# LV_solo_mission_schematic.net
KiCad netlist of a schematic drawn in Altium Designer
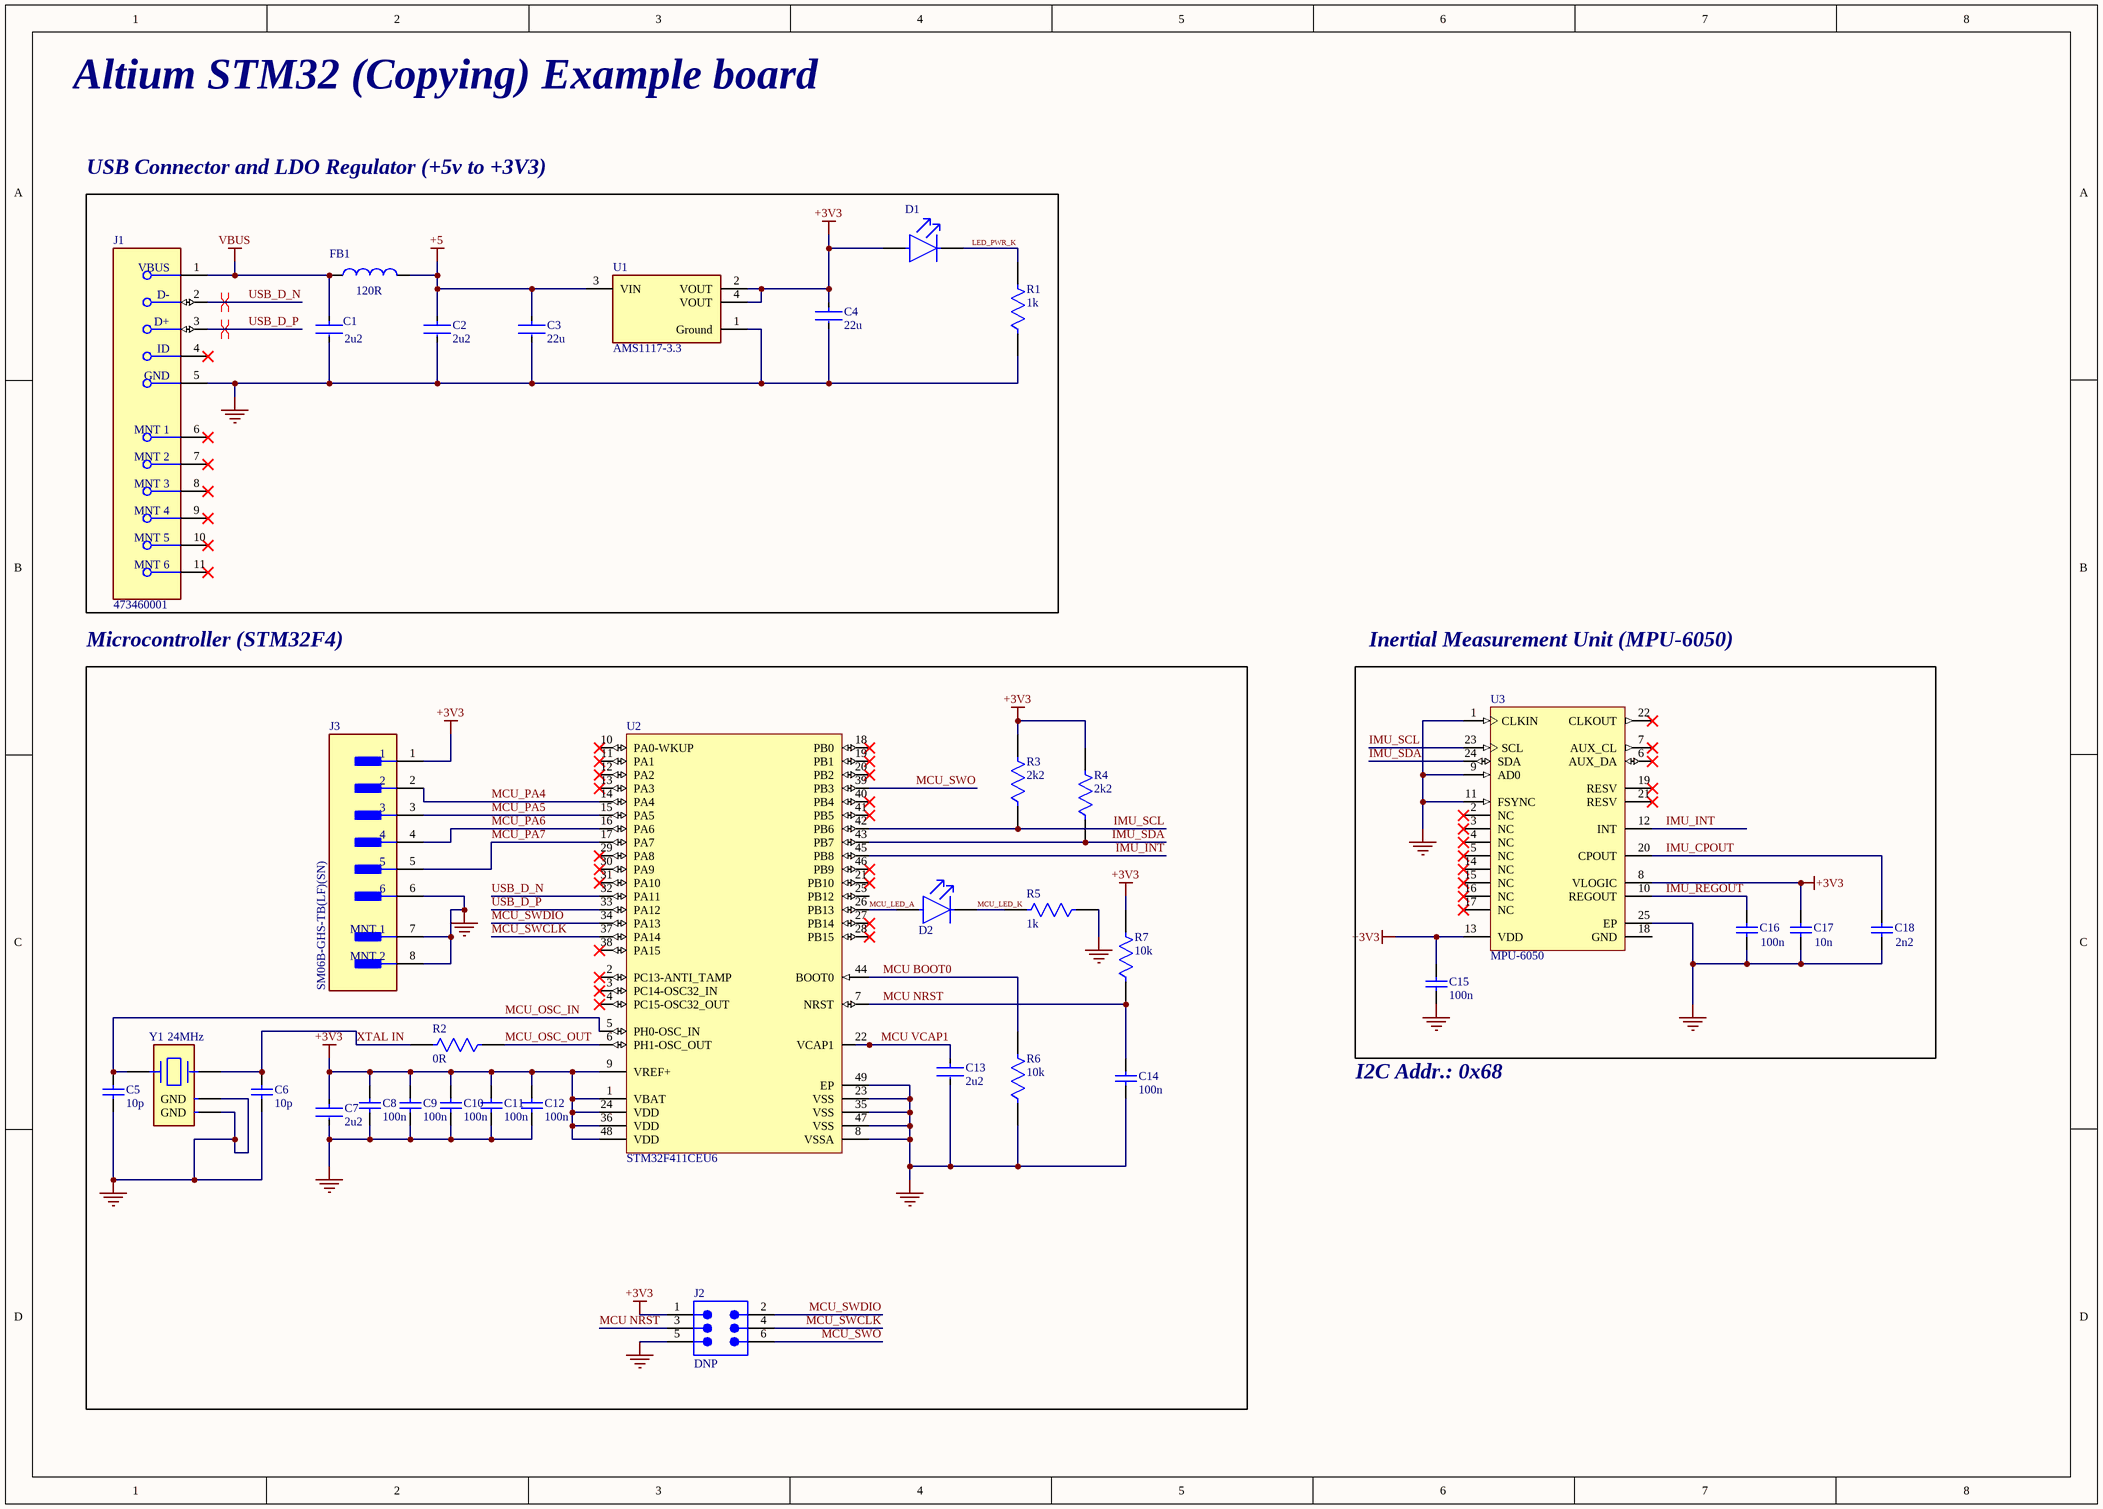
[diagram p0: LV solo mission schematic.SchDoc]

(export (version "E")
  (design (tool "Eeschema 10.0.6"))
  (components
    (comp (ref "C1")
      (value "2u2")
      (footprint "FP-GRM188-0_2-IPC_B")
      (description "CAP CER 2.2UF 16V X7S 0603")
      (fields (field (name "TOLERANCE") "10%"))
      (libsource (lib "Altium Content Vault") (part "b4654b650e69147ec39a6b967a45e02"))
    )
    (comp (ref "C2")
      (value "2u2")
      (footprint "FP-GRM188-0_2-IPC_B")
      (description "CAP CER 2.2UF 16V X7S 0603")
      (fields (field (name "TOLERANCE") "10%"))
      (libsource (lib "Altium Content Vault") (part "b4654b650e69147ec39a6b967a45e02"))
    )
    (comp (ref "C3")
      (value "22u")
      (footprint "FP-GRM21B-0_2-e0_2_0_7-MFG")
      (description "Chip Multilayer Ceramic Capacitors for General Purpose, 0805, 22uF, X6S, 22%, 20%, 16V")
      (fields (field (name "TOLERANCE") "20%"))
      (libsource (lib "Altium Content Vault") (part "b4654b650e69147ec39a6b967a45e02"))
    )
    (comp (ref "C4")
      (value "22u")
      (footprint "FP-GRM21B-0_2-e0_2_0_7-MFG")
      (description "Chip Multilayer Ceramic Capacitors for General Purpose, 0805, 22uF, X6S, 22%, 20%, 16V")
      (fields (field (name "TOLERANCE") "20%"))
      (libsource (lib "Altium Content Vault") (part "b4654b650e69147ec39a6b967a45e02"))
    )
    (comp (ref "C5")
      (value "10p")
      (footprint "CAPC1005X55X25LL05T05")
      (fields (field (name "PART NUMBER") "VJ0402A100KXJCW1BC") (field (name "MANUFACTURER") "Vitramon"))
      (libsource (lib "Altium Content Vault") (part "CAP"))
    )
    (comp (ref "C6")
      (value "10p")
      (footprint "CAPC1005X55X25LL05T05")
      (fields (field (name "PART NUMBER") "VJ0402A100KXJCW1BC") (field (name "MANUFACTURER") "Vitramon"))
      (libsource (lib "Altium Content Vault") (part "CAP"))
    )
    (comp (ref "C7")
      (value "2u2")
      (footprint "FP-GRM188-0_2-IPC_B")
      (description "CAP CER 2.2UF 16V X7S 0603")
      (fields (field (name "TOLERANCE") "10%"))
      (libsource (lib "Altium Content Vault") (part "b4654b650e69147ec39a6b967a45e02"))
    )
    (comp (ref "C8")
      (value "100n")
      (footprint "CAPC1005X55X30NL05T10")
      (fields (field (name "PART NUMBER") "C0402C104K4RALTU") (field (name "MANUFACTURER") "Kemet"))
      (libsource (lib "Altium Content Vault") (part "CAP"))
    )
    (comp (ref "C9")
      (value "100n")
      (footprint "CAPC1005X55X30NL05T10")
      (fields (field (name "PART NUMBER") "C0402C104K4RALTU") (field (name "MANUFACTURER") "Kemet"))
      (libsource (lib "Altium Content Vault") (part "CAP"))
    )
    (comp (ref "C10")
      (value "100n")
      (footprint "CAPC1005X55X30NL05T10")
      (fields (field (name "PART NUMBER") "C0402C104K4RALTU") (field (name "MANUFACTURER") "Kemet"))
      (libsource (lib "Altium Content Vault") (part "CAP"))
    )
    (comp (ref "C11")
      (value "100n")
      (footprint "CAPC1005X55X30NL05T10")
      (fields (field (name "PART NUMBER") "C0402C104K4RALTU") (field (name "MANUFACTURER") "Kemet"))
      (libsource (lib "Altium Content Vault") (part "CAP"))
    )
    (comp (ref "C12")
      (value "100n")
      (footprint "CAPC1005X55X30NL05T10")
      (fields (field (name "PART NUMBER") "C0402C104K4RALTU") (field (name "MANUFACTURER") "Kemet"))
      (libsource (lib "Altium Content Vault") (part "CAP"))
    )
    (comp (ref "C13")
      (value "2u2")
      (footprint "FP-GRM188-0_2-IPC_B")
      (description "CAP CER 2.2UF 16V X7S 0603")
      (fields (field (name "TOLERANCE") "10%"))
      (libsource (lib "Altium Content Vault") (part "b4654b650e69147ec39a6b967a45e02"))
    )
    (comp (ref "C14")
      (value "100n")
      (footprint "CAPC1005X55X30NL05T10")
      (fields (field (name "PART NUMBER") "C0402C104K4RALTU") (field (name "MANUFACTURER") "Kemet"))
      (libsource (lib "Altium Content Vault") (part "CAP"))
    )
    (comp (ref "C15")
      (value "100n")
      (footprint "CAPC1005X55X30NL05T10")
      (fields (field (name "PART NUMBER") "C0402C104K4RALTU") (field (name "MANUFACTURER") "Kemet"))
      (libsource (lib "Altium Content Vault") (part "CAP"))
    )
    (comp (ref "C16")
      (value "100n")
      (footprint "CAPC1005X55X30NL05T10")
      (fields (field (name "PART NUMBER") "C0402C104K4RALTU") (field (name "MANUFACTURER") "Kemet"))
      (libsource (lib "Altium Content Vault") (part "CAP"))
    )
    (comp (ref "C17")
      (value "10n")
      (footprint "CAPC1005X55X30NL05T10")
      (fields (field (name "PART NUMBER") "C0402C104K4RALTU") (field (name "MANUFACTURER") "Kemet"))
      (libsource (lib "Altium Content Vault") (part "CAP"))
    )
    (comp (ref "C18")
      (value "2n2")
      (footprint "CAPC1005X55X30NL05T10")
      (fields (field (name "PART NUMBER") "C0402C104K4RALTU") (field (name "MANUFACTURER") "Kemet"))
      (libsource (lib "Altium Content Vault") (part "CAP"))
    )
    (comp (ref "D1")
      (value "~")
      (footprint "FP-APG1005CGC-T-MFG")
      (description "LED GREEN CLEAR CHIP SMD")
      (libsource (lib "Altium Content Vault") (part "8706943c75ba83719d021d2fdc84c58"))
    )
    (comp (ref "D2")
      (value "APHHS1005SURCK")
      (footprint "FP-APHHS1005SURCK-MFG")
      (description "LED RED CLEAR CHIP SMD")
      (libsource (lib "Altium Content Vault") (part "8706943c75ba83719d021d2fdc84c58"))
    )
    (comp (ref "FB1")
      (value "120R")
      (footprint "WE-CBF HF_0603_HC")
      (description "Ferrite Bead (emi Suppression), 1.6X0.8X0.8MM (0603), 600O Impedance At 100 Mhz")
      (fields (field (name "TOLERANCE") "25%"))
      (libsource (lib "Altium Content Vault") (part "Ferrite"))
    )
    (comp (ref "J1")
      (value "473460001")
      (footprint "FP-473460001-MFG")
      (description "CONN RCPT USB2.0 MICRO B SMD R/A")
      (fields
        (field (name "OCTOPART") "https://octopart.com/47346-0001-molex-7164928")
        (field (name "MANUFACTURER") "Molex")
      )
      (libsource (lib "Altium Content Vault") (part "53ae1f1d9b557310b43ca686e5bb76a"))
    )
    (comp (ref "J2")
      (value "DNP")
      (footprint "61300621121")
      (description "THT Vertical Pin Header WR-PHD, Pitch 2.54 mm, Dual Row, 6 pins")
      (libsource (lib "Altium Content Vault") (part "Header_Male_2R_06P"))
    )
    (comp (ref "J3")
      (value "SM06B-GHS-TB(LF)(SN)")
      (footprint "FP-SM06B-GHS-TB_LF_SN-MFG")
      (description "CONN HEADER SMD R/A 6POS 1.25MM")
      (libsource (lib "Altium Content Vault") (part "ed24c53d9ba001d1a2a686240a95171"))
    )
    (comp (ref "R1")
      (value "1k")
      (footprint "FP-CR0402-MFG")
      (description "Sulfur-Resistant, AEC-Q200 Compliant Chip Resistors 0402 10kΩ 0.063W 1% 100ppm/°C")
      (libsource (lib "Altium Content Vault") (part "1029c3af85768c4190bb7ad29bc67b5"))
    )
    (comp (ref "R2")
      (value "0R")
      (footprint "FP-CR0402-MFG")
      (description "Sulfur-Resistant, AEC-Q200 Compliant Chip Resistors 0402 10kΩ 0.063W 1% 100ppm/°C")
      (libsource (lib "Altium Content Vault") (part "1029c3af85768c4190bb7ad29bc67b5"))
    )
    (comp (ref "R3")
      (value "2k2")
      (footprint "FP-CR0402-MFG")
      (description "Sulfur-Resistant, AEC-Q200 Compliant Chip Resistors 0402 10kΩ 0.063W 1% 100ppm/°C")
      (libsource (lib "Altium Content Vault") (part "1029c3af85768c4190bb7ad29bc67b5"))
    )
    (comp (ref "R4")
      (value "2k2")
      (footprint "FP-CR0402-MFG")
      (description "Sulfur-Resistant, AEC-Q200 Compliant Chip Resistors 0402 10kΩ 0.063W 1% 100ppm/°C")
      (libsource (lib "Altium Content Vault") (part "1029c3af85768c4190bb7ad29bc67b5"))
    )
    (comp (ref "R5")
      (value "1k")
      (footprint "FP-CR0402-MFG")
      (description "Sulfur-Resistant, AEC-Q200 Compliant Chip Resistors 0402 10kΩ 0.063W 1% 100ppm/°C")
      (libsource (lib "Altium Content Vault") (part "1029c3af85768c4190bb7ad29bc67b5"))
    )
    (comp (ref "R6")
      (value "10k")
      (footprint "FP-CR0402-MFG")
      (description "Sulfur-Resistant, AEC-Q200 Compliant Chip Resistors 0402 10kΩ 0.063W 1% 100ppm/°C")
      (libsource (lib "Altium Content Vault") (part "1029c3af85768c4190bb7ad29bc67b5"))
    )
    (comp (ref "R7")
      (value "10k")
      (footprint "FP-CR0402-MFG")
      (description "Sulfur-Resistant, AEC-Q200 Compliant Chip Resistors 0402 10kΩ 0.063W 1% 100ppm/°C")
      (libsource (lib "Altium Content Vault") (part "1029c3af85768c4190bb7ad29bc67b5"))
    )
    (comp (ref "U1")
      (value "AMS1117-3.3")
      (footprint "FP-AMS1117-IPC_C")
      (description "LDO Voltage Regulators 1A, 3.3V")
      (fields
        (field (name "OCTOPART") "https://octopart.com/ams1117-3.3-advanced+monolithic+systems-25899300")
        (field (name "MANUFACTURER") "Advanced Monolithic Systems")
      )
      (libsource (lib "Altium Content Vault") (part "8bdbb5f8e77002000e30dd2845d0354"))
    )
    (comp (ref "U2")
      (value "STM32F411CEU6")
      (footprint "STM-UFQFPN48_L")
      (libsource (lib "Altium Content Vault") (part "MC-ARM-STM32F411-UFQFPN48"))
    )
    (comp (ref "U3")
      (value "MPU-6050")
      (footprint "IS-QFN-24_V")
      (fields (field (name "MANUFACTURER") "InvenSense"))
      (libsource (lib "Altium Content Vault") (part "IS-MPU-6050-QFN-24"))
    )
    (comp (ref "Y1")
      (value "24MHz")
      (footprint "FP-ABM8W-MFG")
      (description "Crystal 24MHz ±10ppm (Tol) ±10ppm (Stability) 7pF FUND 50Ω 4-Pin SMD T/R")
      (libsource (lib "Altium Content Vault") (part "41079aabb0e87794b56622915be14ed"))
    )
  )
  (nets
    (net (code "1") (name "+3V3") (class "Default")
      (node (ref "C10") (pin "1") (pinfunction "1_1") (pintype "passive"))
      (node (ref "C11") (pin "1") (pinfunction "1_1") (pintype "passive"))
      (node (ref "C12") (pin "1") (pinfunction "1_1") (pintype "passive"))
      (node (ref "C15") (pin "1") (pinfunction "1_1") (pintype "passive"))
      (node (ref "C17") (pin "1") (pinfunction "1_1") (pintype "passive"))
      (node (ref "C4") (pin "1") (pinfunction "1_1") (pintype "passive"))
      (node (ref "C7") (pin "1") (pinfunction "1_1") (pintype "passive"))
      (node (ref "C8") (pin "1") (pinfunction "1_1") (pintype "passive"))
      (node (ref "C9") (pin "1") (pinfunction "1_1") (pintype "passive"))
      (node (ref "D1") (pin "2") (pinfunction "A_2") (pintype "passive"))
      (node (ref "J2") (pin "1") (pinfunction "1_1") (pintype "passive"))
      (node (ref "J3") (pin "1") (pinfunction "1_1") (pintype "passive"))
      (node (ref "R3") (pin "2") (pinfunction "2_2") (pintype "passive"))
      (node (ref "R4") (pin "2") (pinfunction "2_2") (pintype "passive"))
      (node (ref "R7") (pin "2") (pinfunction "2_2") (pintype "passive"))
      (node (ref "U1") (pin "2") (pinfunction "VOUT_2") (pintype "passive"))
      (node (ref "U1") (pin "4") (pinfunction "VOUT_4") (pintype "passive"))
      (node (ref "U2") (pin "1") (pinfunction "VBAT_1") (pintype "power_in"))
      (node (ref "U2") (pin "24") (pinfunction "VDD_24") (pintype "power_in"))
      (node (ref "U2") (pin "36") (pinfunction "VDD_36") (pintype "power_in"))
      (node (ref "U2") (pin "48") (pinfunction "VDD_48") (pintype "power_in"))
      (node (ref "U2") (pin "9") (pinfunction "VREF+_9") (pintype "power_in"))
      (node (ref "U3") (pin "13") (pinfunction "VDD_13") (pintype "power_in"))
      (node (ref "U3") (pin "8") (pinfunction "VLOGIC_8") (pintype "power_in"))
    )
    (net (code "2") (name "+5") (class "Default")
      (node (ref "C2") (pin "1") (pinfunction "1_1") (pintype "passive"))
      (node (ref "C3") (pin "1") (pinfunction "1_1") (pintype "passive"))
      (node (ref "FB1") (pin "2") (pinfunction "2_2") (pintype "passive"))
      (node (ref "U1") (pin "3") (pinfunction "VIN_3") (pintype "power_in"))
    )
    (net (code "3") (name "/IMU_CPOUT") (class "Default")
      (node (ref "C18") (pin "1") (pinfunction "1_1") (pintype "passive"))
      (node (ref "U3") (pin "20") (pinfunction "CPOUT_20") (pintype "passive"))
    )
    (net (code "4") (name "/IMU_INT") (class "Default")
      (node (ref "U2") (pin "45") (pinfunction "PB8_45") (pintype "bidirectional"))
      (node (ref "U3") (pin "12") (pinfunction "INT_12") (pintype "open_collector"))
    )
    (net (code "5") (name "/IMU_REGOUT") (class "Default")
      (node (ref "C16") (pin "1") (pinfunction "1_1") (pintype "passive"))
      (node (ref "U3") (pin "10") (pinfunction "REGOUT_10") (pintype "passive"))
    )
    (net (code "6") (name "/IMU_SCL") (class "Default")
      (node (ref "R3") (pin "1") (pinfunction "1_1") (pintype "passive"))
      (node (ref "U2") (pin "42") (pinfunction "PB6_42") (pintype "bidirectional"))
      (node (ref "U3") (pin "23") (pinfunction "SCL_23") (pintype "input"))
    )
    (net (code "7") (name "/IMU_SDA") (class "Default")
      (node (ref "R4") (pin "1") (pinfunction "1_1") (pintype "passive"))
      (node (ref "U2") (pin "43") (pinfunction "PB7_43") (pintype "bidirectional"))
      (node (ref "U3") (pin "24") (pinfunction "SDA_24") (pintype "bidirectional"))
    )
    (net (code "8") (name "/LED_PWR_K") (class "Default")
      (node (ref "D1") (pin "1") (pinfunction "C_1") (pintype "passive"))
      (node (ref "R1") (pin "2") (pinfunction "2_2") (pintype "passive"))
    )
    (net (code "9") (name "/MCU BOOT0") (class "Default")
      (node (ref "R6") (pin "2") (pinfunction "2_2") (pintype "passive"))
      (node (ref "U2") (pin "44") (pinfunction "BOOT0_44") (pintype "input"))
    )
    (net (code "10") (name "/MCU NRST") (class "Default")
      (node (ref "C14") (pin "1") (pinfunction "1_1") (pintype "passive"))
      (node (ref "J2") (pin "3") (pinfunction "3_3") (pintype "passive"))
      (node (ref "R7") (pin "1") (pinfunction "1_1") (pintype "passive"))
      (node (ref "U2") (pin "7") (pinfunction "NRST_7") (pintype "bidirectional"))
    )
    (net (code "11") (name "/MCU VCAP1") (class "Default")
      (node (ref "C13") (pin "1") (pinfunction "1_1") (pintype "passive"))
      (node (ref "U2") (pin "22") (pinfunction "VCAP1_22") (pintype "passive"))
    )
    (net (code "12") (name "/MCU_LED_A") (class "Default")
      (node (ref "D2") (pin "2") (pinfunction "A_2") (pintype "passive"))
      (node (ref "U2") (pin "26") (pinfunction "PB13_26") (pintype "bidirectional"))
    )
    (net (code "13") (name "/MCU_LED_K") (class "Default")
      (node (ref "D2") (pin "1") (pinfunction "C_1") (pintype "passive"))
      (node (ref "R5") (pin "2") (pinfunction "2_2") (pintype "passive"))
    )
    (net (code "14") (name "/MCU_OSC_IN") (class "Default")
      (node (ref "C5") (pin "2") (pinfunction "2_2") (pintype "passive"))
      (node (ref "U2") (pin "5") (pinfunction "PH0-OSC_IN_5") (pintype "bidirectional"))
      (node (ref "Y1") (pin "1") (pinfunction "1_1") (pintype "passive"))
    )
    (net (code "15") (name "/MCU_OSC_OUT") (class "Default")
      (node (ref "R2") (pin "1") (pinfunction "1_1") (pintype "passive"))
      (node (ref "U2") (pin "6") (pinfunction "PH1-OSC_OUT_6") (pintype "bidirectional"))
    )
    (net (code "16") (name "/MCU_PA4") (class "Default")
      (node (ref "J3") (pin "2") (pinfunction "2_2") (pintype "passive"))
      (node (ref "U2") (pin "14") (pinfunction "PA4_14") (pintype "bidirectional"))
    )
    (net (code "17") (name "/MCU_PA5") (class "Default")
      (node (ref "J3") (pin "3") (pinfunction "3_3") (pintype "passive"))
      (node (ref "U2") (pin "15") (pinfunction "PA5_15") (pintype "bidirectional"))
    )
    (net (code "18") (name "/MCU_PA6") (class "Default")
      (node (ref "J3") (pin "4") (pinfunction "4_4") (pintype "passive"))
      (node (ref "U2") (pin "16") (pinfunction "PA6_16") (pintype "bidirectional"))
    )
    (net (code "19") (name "/MCU_PA7") (class "Default")
      (node (ref "J3") (pin "5") (pinfunction "5_5") (pintype "passive"))
      (node (ref "U2") (pin "17") (pinfunction "PA7_17") (pintype "bidirectional"))
    )
    (net (code "20") (name "/MCU_SWCLK") (class "Default")
      (node (ref "J2") (pin "4") (pinfunction "4_4") (pintype "passive"))
      (node (ref "U2") (pin "37") (pinfunction "PA14_37") (pintype "bidirectional"))
    )
    (net (code "21") (name "/MCU_SWDIO") (class "Default")
      (node (ref "J2") (pin "2") (pinfunction "2_2") (pintype "passive"))
      (node (ref "U2") (pin "34") (pinfunction "PA13_34") (pintype "bidirectional"))
    )
    (net (code "22") (name "/MCU_SWO") (class "Default")
      (node (ref "J2") (pin "6") (pinfunction "6_6") (pintype "passive"))
      (node (ref "U2") (pin "39") (pinfunction "PB3_39") (pintype "bidirectional"))
    )
    (net (code "23") (name "/USB_D_N") (class "Default")
      (node (ref "J1") (pin "2") (pinfunction "D-_2") (pintype "bidirectional"))
      (node (ref "U2") (pin "32") (pinfunction "PA11_32") (pintype "bidirectional"))
    )
    (net (code "24") (name "/USB_D_P") (class "Default")
      (node (ref "J1") (pin "3") (pinfunction "D+_3") (pintype "bidirectional"))
      (node (ref "U2") (pin "33") (pinfunction "PA12_33") (pintype "bidirectional"))
    )
    (net (code "25") (name "/XTAL IN") (class "Default")
      (node (ref "C6") (pin "2") (pinfunction "2_2") (pintype "passive"))
      (node (ref "R2") (pin "2") (pinfunction "2_2") (pintype "passive"))
      (node (ref "Y1") (pin "3") (pinfunction "3_3") (pintype "passive"))
    )
    (net (code "26") (name "GND") (class "Default")
      (node (ref "C1") (pin "2") (pinfunction "2_2") (pintype "passive"))
      (node (ref "C10") (pin "2") (pinfunction "2_2") (pintype "passive"))
      (node (ref "C11") (pin "2") (pinfunction "2_2") (pintype "passive"))
      (node (ref "C12") (pin "2") (pinfunction "2_2") (pintype "passive"))
      (node (ref "C13") (pin "2") (pinfunction "2_2") (pintype "passive"))
      (node (ref "C14") (pin "2") (pinfunction "2_2") (pintype "passive"))
      (node (ref "C15") (pin "2") (pinfunction "2_2") (pintype "passive"))
      (node (ref "C16") (pin "2") (pinfunction "2_2") (pintype "passive"))
      (node (ref "C17") (pin "2") (pinfunction "2_2") (pintype "passive"))
      (node (ref "C18") (pin "2") (pinfunction "2_2") (pintype "passive"))
      (node (ref "C2") (pin "2") (pinfunction "2_2") (pintype "passive"))
      (node (ref "C3") (pin "2") (pinfunction "2_2") (pintype "passive"))
      (node (ref "C4") (pin "2") (pinfunction "2_2") (pintype "passive"))
      (node (ref "C5") (pin "1") (pinfunction "1_1") (pintype "passive"))
      (node (ref "C6") (pin "1") (pinfunction "1_1") (pintype "passive"))
      (node (ref "C7") (pin "2") (pinfunction "2_2") (pintype "passive"))
      (node (ref "C8") (pin "2") (pinfunction "2_2") (pintype "passive"))
      (node (ref "C9") (pin "2") (pinfunction "2_2") (pintype "passive"))
      (node (ref "J1") (pin "5") (pinfunction "GND_5") (pintype "power_in"))
      (node (ref "J2") (pin "5") (pinfunction "5_5") (pintype "passive"))
      (node (ref "J3") (pin "6") (pinfunction "6_6") (pintype "passive"))
      (node (ref "J3") (pin "7") (pinfunction "MNT_1_7") (pintype "passive"))
      (node (ref "J3") (pin "8") (pinfunction "MNT_2_8") (pintype "passive"))
      (node (ref "R1") (pin "1") (pinfunction "1_1") (pintype "passive"))
      (node (ref "R5") (pin "1") (pinfunction "1_1") (pintype "passive"))
      (node (ref "R6") (pin "1") (pinfunction "1_1") (pintype "passive"))
      (node (ref "U1") (pin "1") (pinfunction "Ground_1") (pintype "power_in"))
      (node (ref "U2") (pin "23") (pinfunction "VSS_23") (pintype "power_in"))
      (node (ref "U2") (pin "35") (pinfunction "VSS_35") (pintype "power_in"))
      (node (ref "U2") (pin "47") (pinfunction "VSS_47") (pintype "power_in"))
      (node (ref "U2") (pin "49") (pinfunction "EP_49") (pintype "power_in"))
      (node (ref "U2") (pin "8") (pinfunction "VSSA_8") (pintype "power_in"))
      (node (ref "U3") (pin "1") (pinfunction "CLKIN_1") (pintype "input"))
      (node (ref "U3") (pin "11") (pinfunction "FSYNC_11") (pintype "input"))
      (node (ref "U3") (pin "25") (pinfunction "EP_25") (pintype "power_in"))
      (node (ref "U3") (pin "9") (pinfunction "AD0_9") (pintype "input"))
      (node (ref "Y1") (pin "2") (pinfunction "GND_2") (pintype "power_in"))
      (node (ref "Y1") (pin "4") (pinfunction "GND_4") (pintype "power_in"))
    )
    (net (code "27") (name "VBUS") (class "Default")
      (node (ref "C1") (pin "1") (pinfunction "1_1") (pintype "passive"))
      (node (ref "FB1") (pin "1") (pinfunction "1_1") (pintype "passive"))
      (node (ref "J1") (pin "1") (pinfunction "VBUS_1") (pintype "power_in"))
    )
    (net (code "28") (name "unconnected-(J1-ID-Pad4)") (class "Default")
      (node (ref "J1") (pin "4") (pinfunction "ID_4") (pintype "passive+no_connect"))
    )
    (net (code "29") (name "unconnected-(J1-MNT_1-Pad6)") (class "Default")
      (node (ref "J1") (pin "6") (pinfunction "MNT_1_6") (pintype "passive+no_connect"))
    )
    (net (code "30") (name "unconnected-(J1-MNT_2-Pad7)") (class "Default")
      (node (ref "J1") (pin "7") (pinfunction "MNT_2_7") (pintype "passive+no_connect"))
    )
    (net (code "31") (name "unconnected-(J1-MNT_3-Pad8)") (class "Default")
      (node (ref "J1") (pin "8") (pinfunction "MNT_3_8") (pintype "passive+no_connect"))
    )
    (net (code "32") (name "unconnected-(J1-MNT_4-Pad9)") (class "Default")
      (node (ref "J1") (pin "9") (pinfunction "MNT_4_9") (pintype "passive+no_connect"))
    )
    (net (code "33") (name "unconnected-(J1-MNT_5-Pad10)") (class "Default")
      (node (ref "J1") (pin "10") (pinfunction "MNT_5_10") (pintype "passive+no_connect"))
    )
    (net (code "34") (name "unconnected-(J1-MNT_6-Pad11)") (class "Default")
      (node (ref "J1") (pin "11") (pinfunction "MNT_6_11") (pintype "passive+no_connect"))
    )
    (net (code "35") (name "unconnected-(U2-PA0-WKUP-Pad10)") (class "Default")
      (node (ref "U2") (pin "10") (pinfunction "PA0-WKUP_10") (pintype "bidirectional+no_connect"))
    )
    (net (code "36") (name "unconnected-(U2-PA1-Pad11)") (class "Default")
      (node (ref "U2") (pin "11") (pinfunction "PA1_11") (pintype "bidirectional+no_connect"))
    )
    (net (code "37") (name "unconnected-(U2-PA2-Pad12)") (class "Default")
      (node (ref "U2") (pin "12") (pinfunction "PA2_12") (pintype "bidirectional+no_connect"))
    )
    (net (code "38") (name "unconnected-(U2-PA3-Pad13)") (class "Default")
      (node (ref "U2") (pin "13") (pinfunction "PA3_13") (pintype "bidirectional+no_connect"))
    )
    (net (code "39") (name "unconnected-(U2-PA8-Pad29)") (class "Default")
      (node (ref "U2") (pin "29") (pinfunction "PA8_29") (pintype "bidirectional+no_connect"))
    )
    (net (code "40") (name "unconnected-(U2-PA9-Pad30)") (class "Default")
      (node (ref "U2") (pin "30") (pinfunction "PA9_30") (pintype "bidirectional+no_connect"))
    )
    (net (code "41") (name "unconnected-(U2-PA10-Pad31)") (class "Default")
      (node (ref "U2") (pin "31") (pinfunction "PA10_31") (pintype "bidirectional+no_connect"))
    )
    (net (code "42") (name "unconnected-(U2-PA15-Pad38)") (class "Default")
      (node (ref "U2") (pin "38") (pinfunction "PA15_38") (pintype "bidirectional+no_connect"))
    )
    (net (code "43") (name "unconnected-(U2-PB0-Pad18)") (class "Default")
      (node (ref "U2") (pin "18") (pinfunction "PB0_18") (pintype "bidirectional+no_connect"))
    )
    (net (code "44") (name "unconnected-(U2-PB1-Pad19)") (class "Default")
      (node (ref "U2") (pin "19") (pinfunction "PB1_19") (pintype "bidirectional+no_connect"))
    )
    (net (code "45") (name "unconnected-(U2-PB2-Pad20)") (class "Default")
      (node (ref "U2") (pin "20") (pinfunction "PB2_20") (pintype "bidirectional+no_connect"))
    )
    (net (code "46") (name "unconnected-(U2-PB4-Pad40)") (class "Default")
      (node (ref "U2") (pin "40") (pinfunction "PB4_40") (pintype "bidirectional+no_connect"))
    )
    (net (code "47") (name "unconnected-(U2-PB5-Pad41)") (class "Default")
      (node (ref "U2") (pin "41") (pinfunction "PB5_41") (pintype "bidirectional+no_connect"))
    )
    (net (code "48") (name "unconnected-(U2-PB9-Pad46)") (class "Default")
      (node (ref "U2") (pin "46") (pinfunction "PB9_46") (pintype "bidirectional+no_connect"))
    )
    (net (code "49") (name "unconnected-(U2-PB10-Pad21)") (class "Default")
      (node (ref "U2") (pin "21") (pinfunction "PB10_21") (pintype "bidirectional+no_connect"))
    )
    (net (code "50") (name "unconnected-(U2-PB12-Pad25)") (class "Default")
      (node (ref "U2") (pin "25") (pinfunction "PB12_25") (pintype "bidirectional"))
    )
    (net (code "51") (name "unconnected-(U2-PB14-Pad27)") (class "Default")
      (node (ref "U2") (pin "27") (pinfunction "PB14_27") (pintype "bidirectional+no_connect"))
    )
    (net (code "52") (name "unconnected-(U2-PB15-Pad28)") (class "Default")
      (node (ref "U2") (pin "28") (pinfunction "PB15_28") (pintype "bidirectional+no_connect"))
    )
    (net (code "53") (name "unconnected-(U2-PC13-ANTI_TAMP-Pad2)") (class "Default")
      (node (ref "U2") (pin "2") (pinfunction "PC13-ANTI_TAMP_2") (pintype "bidirectional+no_connect"))
    )
    (net (code "54") (name "unconnected-(U2-PC14-OSC32_IN-Pad3)") (class "Default")
      (node (ref "U2") (pin "3") (pinfunction "PC14-OSC32_IN_3") (pintype "bidirectional+no_connect"))
    )
    (net (code "55") (name "unconnected-(U2-PC15-OSC32_OUT-Pad4)") (class "Default")
      (node (ref "U2") (pin "4") (pinfunction "PC15-OSC32_OUT_4") (pintype "bidirectional+no_connect"))
    )
    (net (code "56") (name "unconnected-(U3-AUX_CL-Pad7)") (class "Default")
      (node (ref "U3") (pin "7") (pinfunction "AUX_CL_7") (pintype "output+no_connect"))
    )
    (net (code "57") (name "unconnected-(U3-AUX_DA-Pad6)") (class "Default")
      (node (ref "U3") (pin "6") (pinfunction "AUX_DA_6") (pintype "bidirectional+no_connect"))
    )
    (net (code "58") (name "unconnected-(U3-CLKOUT-Pad22)") (class "Default")
      (node (ref "U3") (pin "22") (pinfunction "CLKOUT_22") (pintype "output+no_connect"))
    )
    (net (code "59") (name "unconnected-(U3-GND-Pad18)") (class "Default")
      (node (ref "U3") (pin "18") (pinfunction "GND_18") (pintype "power_in"))
    )
    (net (code "60") (name "unconnected-(U3-NC-Pad2)") (class "Default")
      (node (ref "U3") (pin "2") (pinfunction "NC_2") (pintype "passive+no_connect"))
    )
    (net (code "61") (name "unconnected-(U3-NC-Pad3)") (class "Default")
      (node (ref "U3") (pin "3") (pinfunction "NC_3") (pintype "passive+no_connect"))
    )
    (net (code "62") (name "unconnected-(U3-NC-Pad4)") (class "Default")
      (node (ref "U3") (pin "4") (pinfunction "NC_4") (pintype "passive+no_connect"))
    )
    (net (code "63") (name "unconnected-(U3-NC-Pad5)") (class "Default")
      (node (ref "U3") (pin "5") (pinfunction "NC_5") (pintype "passive+no_connect"))
    )
    (net (code "64") (name "unconnected-(U3-NC-Pad14)") (class "Default")
      (node (ref "U3") (pin "14") (pinfunction "NC_14") (pintype "passive+no_connect"))
    )
    (net (code "65") (name "unconnected-(U3-NC-Pad15)") (class "Default")
      (node (ref "U3") (pin "15") (pinfunction "NC_15") (pintype "passive+no_connect"))
    )
    (net (code "66") (name "unconnected-(U3-NC-Pad16)") (class "Default")
      (node (ref "U3") (pin "16") (pinfunction "NC_16") (pintype "passive+no_connect"))
    )
    (net (code "67") (name "unconnected-(U3-NC-Pad17)") (class "Default")
      (node (ref "U3") (pin "17") (pinfunction "NC_17") (pintype "passive+no_connect"))
    )
    (net (code "68") (name "unconnected-(U3-RESV-Pad19)") (class "Default")
      (node (ref "U3") (pin "19") (pinfunction "RESV_19") (pintype "passive+no_connect"))
    )
    (net (code "69") (name "unconnected-(U3-RESV-Pad21)") (class "Default")
      (node (ref "U3") (pin "21") (pinfunction "RESV_21") (pintype "passive+no_connect"))
    )
  )
)
